# klbr4breakout-1.net
KiCad netlist of a schematic drawn in EAGLE
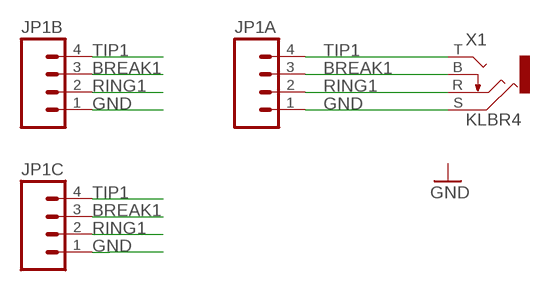
[diagram p0: schematic, sheet 1]

(export (version "E")
  (design (tool "Eeschema 10.0.6"))
  (components
    (comp (ref "JP1A")
      (value "M04PTH")
      (footprint "eagle-import:1X04")
      (libsource (lib "eagle-import") (part "M04PTH"))
    )
    (comp (ref "JP1B")
      (value "M04PTH")
      (footprint "eagle-import:1X04")
      (libsource (lib "eagle-import") (part "M04PTH"))
    )
    (comp (ref "JP1C")
      (value "M04PTH")
      (footprint "eagle-import:1X04")
      (libsource (lib "eagle-import") (part "M04PTH"))
    )
    (comp (ref "X1")
      (value "KLBR4")
      (footprint "eagle-import:KLBR4")
      (libsource (lib "eagle-import") (part "KLBR4"))
    )
  )
  (nets
    (net (code "1") (name "/BREAK1") (class "Default")
      (node (ref "JP1A") (pin "3") (pinfunction "3_3") (pintype "passive"))
      (node (ref "JP1B") (pin "3") (pinfunction "3_3") (pintype "passive"))
      (node (ref "JP1C") (pin "3") (pinfunction "3_3") (pintype "passive"))
      (node (ref "X1") (pin "B") (pinfunction "B_B") (pintype "passive"))
    )
    (net (code "2") (name "/RING1") (class "Default")
      (node (ref "JP1A") (pin "2") (pinfunction "2_2") (pintype "passive"))
      (node (ref "JP1B") (pin "2") (pinfunction "2_2") (pintype "passive"))
      (node (ref "JP1C") (pin "2") (pinfunction "2_2") (pintype "passive"))
      (node (ref "X1") (pin "R") (pinfunction "R_R") (pintype "passive"))
    )
    (net (code "3") (name "/TIP1") (class "Default")
      (node (ref "JP1A") (pin "4") (pinfunction "4_4") (pintype "passive"))
      (node (ref "JP1B") (pin "4") (pinfunction "4_4") (pintype "passive"))
      (node (ref "JP1C") (pin "4") (pinfunction "4_4") (pintype "passive"))
      (node (ref "X1") (pin "T") (pinfunction "T_T") (pintype "passive"))
    )
    (net (code "4") (name "GND") (class "Default")
      (node (ref "JP1A") (pin "1") (pinfunction "1_1") (pintype "passive"))
      (node (ref "JP1B") (pin "1") (pinfunction "1_1") (pintype "passive"))
      (node (ref "JP1C") (pin "1") (pinfunction "1_1") (pintype "passive"))
      (node (ref "X1") (pin "S") (pinfunction "S_S") (pintype "passive"))
    )
  )
)
